# main_board.net
KiCad netlist of a schematic drawn in EAGLE
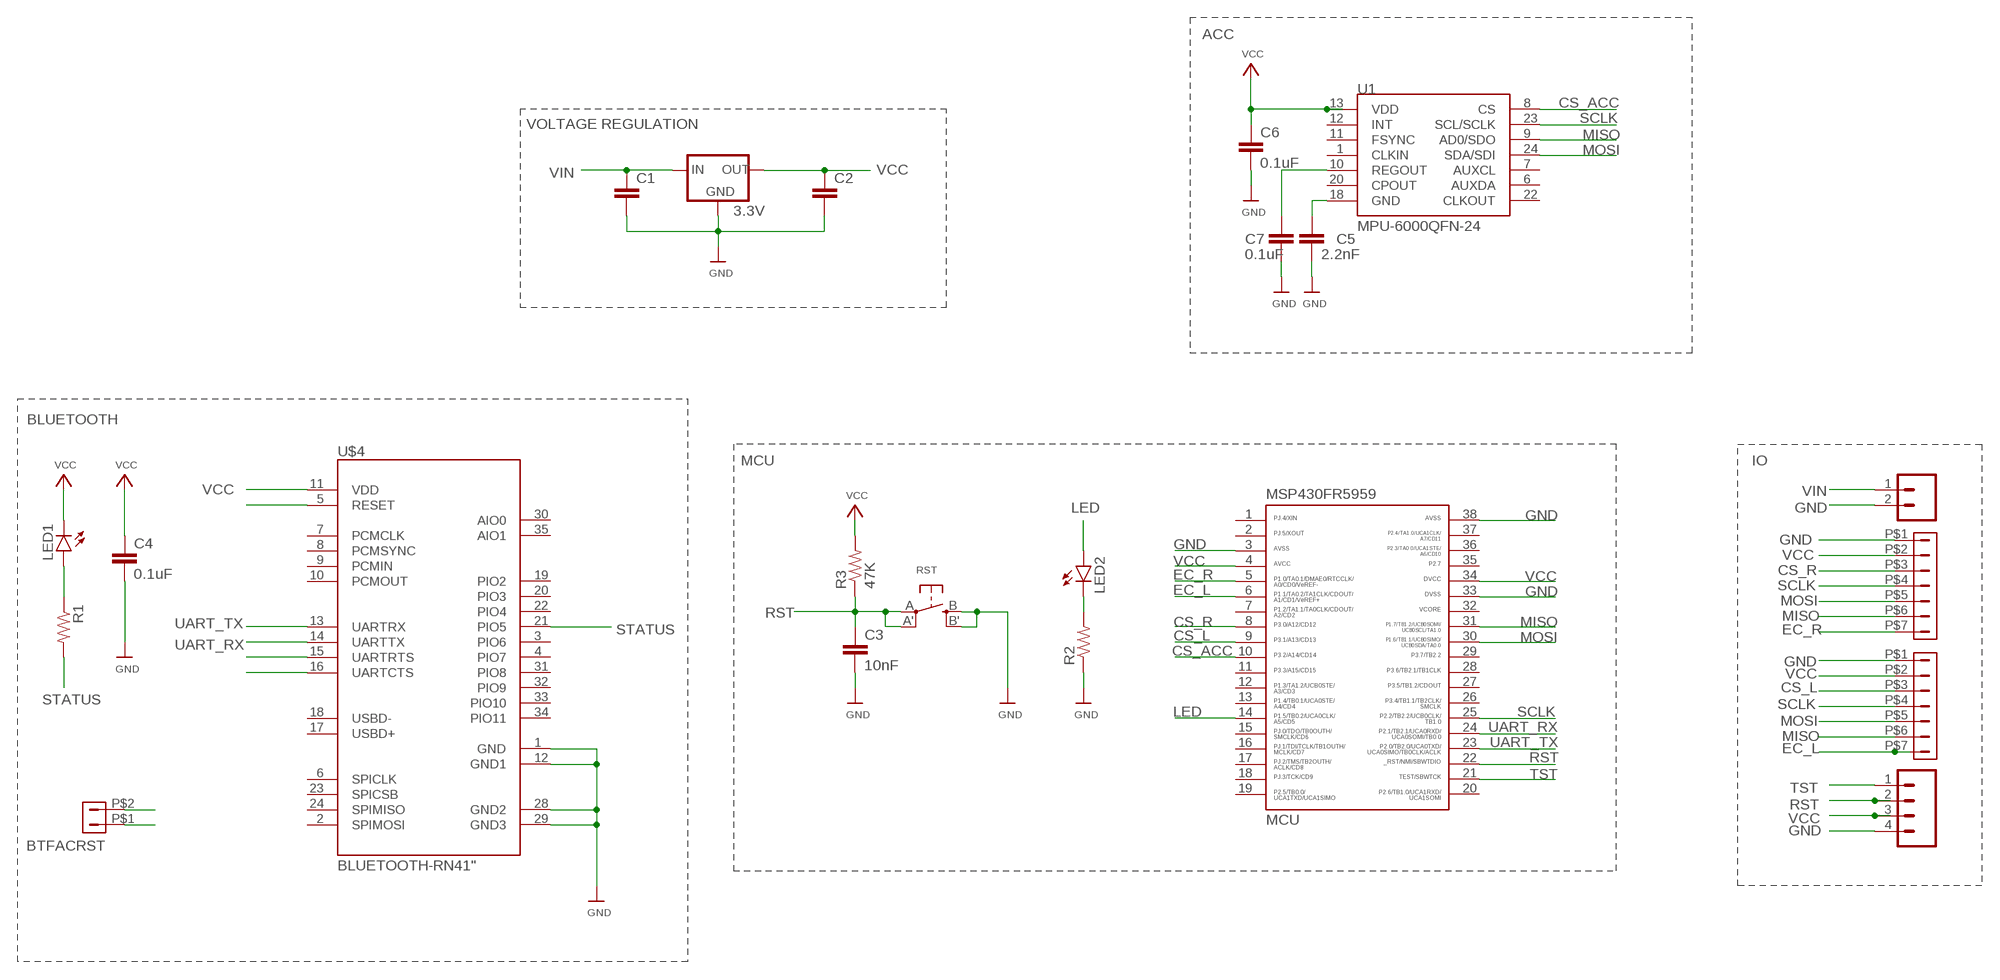
[diagram p0: schematic, sheet 1]

(export (version "E")
  (design (tool "Eeschema 10.0.6"))
  (components
    (comp (ref "3.3V")
      (value "V_REG_78XX")
      (footprint "eagle-import:SOT223")
      (libsource (lib "eagle-import") (part "V_REG_78XX"))
    )
    (comp (ref "5V")
      (value "M02-JST-2-PTH-NO_SILK")
      (footprint "eagle-import:JST-2-PTH-NS")
      (libsource (lib "eagle-import") (part "M02-JST-2-PTH-NO_SILK"))
    )
    (comp (ref "BTFACRST")
      (value "DF13-2P-1.25DSA")
      (footprint "eagle-import:DF13-2P-1.25DSA")
      (libsource (lib "eagle-import") (part "DF13-2P-1.25DSA"))
    )
    (comp (ref "C1")
      (value "CAP0603-CAP")
      (footprint "eagle-import:0603-CAP")
      (libsource (lib "eagle-import") (part "CAP0603-CAP"))
    )
    (comp (ref "C2")
      (value "CAP0603-CAP")
      (footprint "eagle-import:0603-CAP")
      (libsource (lib "eagle-import") (part "CAP0603-CAP"))
    )
    (comp (ref "C3")
      (value "10nF")
      (footprint "eagle-import:0603-CAP")
      (libsource (lib "eagle-import") (part "CAP0603-CAP"))
    )
    (comp (ref "C4")
      (value "0.1uF")
      (footprint "eagle-import:0603-CAP")
      (libsource (lib "eagle-import") (part "CAP0603-CAP"))
    )
    (comp (ref "C5")
      (value "2.2nF")
      (footprint "eagle-import:0402-CAP")
      (libsource (lib "eagle-import") (part "CAP0402-CAP"))
    )
    (comp (ref "C6")
      (value "0.1uF")
      (footprint "eagle-import:0402-CAP")
      (libsource (lib "eagle-import") (part "CAP0402-CAP"))
    )
    (comp (ref "C7")
      (value "0.1uF")
      (footprint "eagle-import:0402-CAP")
      (libsource (lib "eagle-import") (part "CAP0402-CAP"))
    )
    (comp (ref "LED1")
      (value "LED0603")
      (footprint "eagle-import:LED-0603")
      (libsource (lib "eagle-import") (part "LED0603"))
    )
    (comp (ref "LED2")
      (value "LED0603")
      (footprint "eagle-import:LED-0603")
      (libsource (lib "eagle-import") (part "LED0603"))
    )
    (comp (ref "LEFT")
      (value "DF13-7P-1.25DS")
      (footprint "eagle-import:DF13-7P-1.25DS")
      (libsource (lib "eagle-import") (part "DF13-7P-1.25DS"))
    )
    (comp (ref "MCU")
      (value "MSP430FR5959")
      (footprint "eagle-import:TSSOP38_R-PDSO-G38-DA")
      (libsource (lib "eagle-import") (part "MSP430FR5959-38"))
    )
    (comp (ref "PGM")
      (value "M04JST")
      (footprint "eagle-import:1X04-1.5MM_JST")
      (libsource (lib "eagle-import") (part "M04JST"))
    )
    (comp (ref "R1")
      (value "RESISTOR0603-RES")
      (footprint "eagle-import:0603-RES")
      (libsource (lib "eagle-import") (part "RESISTOR0603-RES"))
    )
    (comp (ref "R2")
      (value "RESISTOR0402-RES")
      (footprint "eagle-import:0402-RES")
      (libsource (lib "eagle-import") (part "RESISTOR0402-RES"))
    )
    (comp (ref "R3")
      (value "47K")
      (footprint "eagle-import:0402-RES")
      (libsource (lib "eagle-import") (part "RESISTOR0402-RES"))
    )
    (comp (ref "RIGHT")
      (value "fname")
      (footprint "eagle-import:DF13-7P-1.25DS")
      (libsource (lib "eagle-import") (part "DF13-7P-1.25DS"))
    )
    (comp (ref "RST")
      (value "SWITCH_TACT_SMT")
      (footprint "eagle-import:EVQ-Q2")
      (libsource (lib "eagle-import") (part "SWITCH_TACT_SMT"))
    )
    (comp (ref "U$4")
      (value "BLUETOOTH-RN41\"")
      (footprint "eagle-import:RN41")
      (libsource (lib "eagle-import") (part "BLUETOOTH-RN41{dblquote}"))
    )
    (comp (ref "U1")
      (value "MPU-6000QFN-24")
      (footprint "eagle-import:QFN-24-TESTING")
      (libsource (lib "eagle-import") (part "MPU-6000QFN-24"))
    )
  )
  (nets
    (net (code "1") (name "/BTRST") (class "Default")
      (node (ref "BTFACRST") (pin "P$2") (pinfunction "2_P$2") (pintype "passive"))
      (node (ref "U$4") (pin "5") (pinfunction "RESET_5") (pintype "bidirectional"))
    )
    (net (code "2") (name "/CS_ACC") (class "Default")
      (node (ref "MCU") (pin "10") (pinfunction "10_10") (pintype "bidirectional"))
      (node (ref "U1") (pin "8") (pinfunction "CS_8") (pintype "bidirectional"))
    )
    (net (code "3") (name "/CS_L") (class "Default")
      (node (ref "LEFT") (pin "P$3") (pinfunction "3_P$3") (pintype "passive"))
      (node (ref "MCU") (pin "9") (pinfunction "9_9") (pintype "bidirectional"))
    )
    (net (code "4") (name "/CS_R") (class "Default")
      (node (ref "MCU") (pin "8") (pinfunction "8_8") (pintype "bidirectional"))
      (node (ref "RIGHT") (pin "P$3") (pinfunction "3_P$3") (pintype "passive"))
    )
    (net (code "5") (name "/EC_L") (class "Default")
      (node (ref "LEFT") (pin "P$7") (pinfunction "7_P$7") (pintype "passive"))
      (node (ref "MCU") (pin "6") (pinfunction "6_6") (pintype "bidirectional"))
    )
    (net (code "6") (name "/EC_R") (class "Default")
      (node (ref "MCU") (pin "5") (pinfunction "5_5") (pintype "bidirectional"))
      (node (ref "RIGHT") (pin "P$7") (pinfunction "7_P$7") (pintype "passive"))
    )
    (net (code "7") (name "/LED") (class "Default")
      (node (ref "LED2") (pin "A") (pinfunction "A_A") (pintype "passive"))
      (node (ref "MCU") (pin "14") (pinfunction "14_14") (pintype "bidirectional"))
    )
    (net (code "8") (name "/MISO") (class "Default")
      (node (ref "LEFT") (pin "P$6") (pinfunction "6_P$6") (pintype "passive"))
      (node (ref "MCU") (pin "31") (pinfunction "31_31") (pintype "bidirectional"))
      (node (ref "RIGHT") (pin "P$6") (pinfunction "6_P$6") (pintype "passive"))
      (node (ref "U1") (pin "9") (pinfunction "AD0/SDO_9") (pintype "bidirectional"))
    )
    (net (code "9") (name "/MOSI") (class "Default")
      (node (ref "LEFT") (pin "P$5") (pinfunction "5_P$5") (pintype "passive"))
      (node (ref "MCU") (pin "30") (pinfunction "30_30") (pintype "bidirectional"))
      (node (ref "RIGHT") (pin "P$5") (pinfunction "5_P$5") (pintype "passive"))
      (node (ref "U1") (pin "24") (pinfunction "SDA/SDI_24") (pintype "bidirectional"))
    )
    (net (code "10") (name "/RST") (class "Default")
      (node (ref "C3") (pin "1") (pinfunction "1_1") (pintype "passive"))
      (node (ref "MCU") (pin "22") (pinfunction "22_22") (pintype "bidirectional"))
      (node (ref "PGM") (pin "2") (pinfunction "2_2") (pintype "passive"))
      (node (ref "R3") (pin "1") (pinfunction "1_1") (pintype "passive"))
      (node (ref "RST") (pin "A") (pinfunction "P_A") (pintype "passive"))
      (node (ref "RST") (pin "A'") (pinfunction "P1_A'") (pintype "passive"))
    )
    (net (code "11") (name "/SCLK") (class "Default")
      (node (ref "LEFT") (pin "P$4") (pinfunction "4_P$4") (pintype "passive"))
      (node (ref "MCU") (pin "25") (pinfunction "25_25") (pintype "bidirectional"))
      (node (ref "RIGHT") (pin "P$4") (pinfunction "4_P$4") (pintype "passive"))
      (node (ref "U1") (pin "23") (pinfunction "SCL/SCLK_23") (pintype "bidirectional"))
    )
    (net (code "12") (name "/STATUS") (class "Default")
      (node (ref "R1") (pin "2") (pinfunction "2_2") (pintype "passive"))
      (node (ref "U$4") (pin "21") (pinfunction "PIO5_21") (pintype "bidirectional"))
    )
    (net (code "13") (name "/TST") (class "Default")
      (node (ref "MCU") (pin "21") (pinfunction "21_21") (pintype "bidirectional"))
      (node (ref "PGM") (pin "1") (pinfunction "1_1") (pintype "passive"))
    )
    (net (code "14") (name "/UART_RX") (class "Default")
      (node (ref "MCU") (pin "24") (pinfunction "24_24") (pintype "bidirectional"))
      (node (ref "U$4") (pin "14") (pinfunction "UARTTX_14") (pintype "bidirectional"))
    )
    (net (code "15") (name "/UART_TX") (class "Default")
      (node (ref "MCU") (pin "23") (pinfunction "23_23") (pintype "bidirectional"))
      (node (ref "U$4") (pin "13") (pinfunction "UARTRX_13") (pintype "bidirectional"))
    )
    (net (code "16") (name "/VIN") (class "Default")
      (node (ref "3.3V") (pin "3") (pinfunction "IN_3") (pintype "input"))
      (node (ref "5V") (pin "1") (pinfunction "1_1") (pintype "passive"))
      (node (ref "C1") (pin "1") (pinfunction "1_1") (pintype "passive"))
    )
    (net (code "17") (name "GND") (class "Default")
      (node (ref "3.3V") (pin "2") (pinfunction "GND_2") (pintype "input"))
      (node (ref "3.3V") (pin "4") (pinfunction "GND_4") (pintype "input"))
      (node (ref "5V") (pin "2") (pinfunction "2_2") (pintype "passive"))
      (node (ref "BTFACRST") (pin "P$1") (pinfunction "1_P$1") (pintype "passive"))
      (node (ref "C1") (pin "2") (pinfunction "2_2") (pintype "passive"))
      (node (ref "C2") (pin "2") (pinfunction "2_2") (pintype "passive"))
      (node (ref "C3") (pin "2") (pinfunction "2_2") (pintype "passive"))
      (node (ref "C4") (pin "2") (pinfunction "2_2") (pintype "passive"))
      (node (ref "C5") (pin "2") (pinfunction "2_2") (pintype "passive"))
      (node (ref "C6") (pin "2") (pinfunction "2_2") (pintype "passive"))
      (node (ref "C7") (pin "2") (pinfunction "2_2") (pintype "passive"))
      (node (ref "LEFT") (pin "P$1") (pinfunction "1_P$1") (pintype "passive"))
      (node (ref "MCU") (pin "3") (pinfunction "3_3") (pintype "bidirectional"))
      (node (ref "MCU") (pin "33") (pinfunction "33_33") (pintype "bidirectional"))
      (node (ref "MCU") (pin "38") (pinfunction "38_38") (pintype "bidirectional"))
      (node (ref "PGM") (pin "4") (pinfunction "4_4") (pintype "passive"))
      (node (ref "R2") (pin "1") (pinfunction "1_1") (pintype "passive"))
      (node (ref "RIGHT") (pin "P$1") (pinfunction "1_P$1") (pintype "passive"))
      (node (ref "RST") (pin "B") (pinfunction "S_B") (pintype "passive"))
      (node (ref "RST") (pin "B'") (pinfunction "S1_B'") (pintype "passive"))
      (node (ref "U$4") (pin "1") (pinfunction "GND_1") (pintype "bidirectional"))
      (node (ref "U$4") (pin "12") (pinfunction "GND1_12") (pintype "bidirectional"))
      (node (ref "U$4") (pin "28") (pinfunction "GND2_28") (pintype "bidirectional"))
      (node (ref "U$4") (pin "29") (pinfunction "GND3_29") (pintype "bidirectional"))
    )
    (net (code "18") (name "Net-(LED1-PadA)") (class "Default")
      (node (ref "LED1") (pin "A") (pinfunction "A_A") (pintype "passive"))
      (node (ref "R1") (pin "1") (pinfunction "1_1") (pintype "passive"))
    )
    (net (code "19") (name "Net-(LED2-PadC)") (class "Default")
      (node (ref "LED2") (pin "C") (pinfunction "C_C") (pintype "passive"))
      (node (ref "R2") (pin "2") (pinfunction "2_2") (pintype "passive"))
    )
    (net (code "20") (name "Net-(U1-GND)") (class "Default")
      (node (ref "C5") (pin "1") (pinfunction "1_1") (pintype "passive"))
      (node (ref "U1") (pin "18") (pinfunction "GND_18") (pintype "bidirectional"))
    )
    (net (code "21") (name "Net-(U1-REGOUT)") (class "Default")
      (node (ref "C7") (pin "1") (pinfunction "1_1") (pintype "passive"))
      (node (ref "U1") (pin "10") (pinfunction "REGOUT_10") (pintype "bidirectional"))
    )
    (net (code "22") (name "VCC") (class "Default")
      (node (ref "3.3V") (pin "1") (pinfunction "OUT_1") (pintype "output"))
      (node (ref "C2") (pin "1") (pinfunction "1_1") (pintype "passive"))
      (node (ref "C4") (pin "1") (pinfunction "1_1") (pintype "passive"))
      (node (ref "C6") (pin "1") (pinfunction "1_1") (pintype "passive"))
      (node (ref "LED1") (pin "C") (pinfunction "C_C") (pintype "passive"))
      (node (ref "LEFT") (pin "P$2") (pinfunction "2_P$2") (pintype "passive"))
      (node (ref "MCU") (pin "34") (pinfunction "34_34") (pintype "bidirectional"))
      (node (ref "MCU") (pin "4") (pinfunction "4_4") (pintype "bidirectional"))
      (node (ref "PGM") (pin "3") (pinfunction "3_3") (pintype "passive"))
      (node (ref "R3") (pin "2") (pinfunction "2_2") (pintype "passive"))
      (node (ref "RIGHT") (pin "P$2") (pinfunction "2_P$2") (pintype "passive"))
      (node (ref "U$4") (pin "11") (pinfunction "VDD_11") (pintype "bidirectional"))
      (node (ref "U1") (pin "13") (pinfunction "VDD_13") (pintype "bidirectional"))
    )
    (net (code "23") (name "unconnected-(MCU-Pad1)") (class "Default")
      (node (ref "MCU") (pin "1") (pinfunction "1_1") (pintype "bidirectional"))
    )
    (net (code "24") (name "unconnected-(MCU-Pad2)") (class "Default")
      (node (ref "MCU") (pin "2") (pinfunction "2_2") (pintype "bidirectional"))
    )
    (net (code "25") (name "unconnected-(MCU-Pad7)") (class "Default")
      (node (ref "MCU") (pin "7") (pinfunction "7_7") (pintype "bidirectional"))
    )
    (net (code "26") (name "unconnected-(MCU-Pad11)") (class "Default")
      (node (ref "MCU") (pin "11") (pinfunction "11_11") (pintype "bidirectional"))
    )
    (net (code "27") (name "unconnected-(MCU-Pad12)") (class "Default")
      (node (ref "MCU") (pin "12") (pinfunction "12_12") (pintype "bidirectional"))
    )
    (net (code "28") (name "unconnected-(MCU-Pad13)") (class "Default")
      (node (ref "MCU") (pin "13") (pinfunction "13_13") (pintype "bidirectional"))
    )
    (net (code "29") (name "unconnected-(MCU-Pad15)") (class "Default")
      (node (ref "MCU") (pin "15") (pinfunction "15_15") (pintype "bidirectional"))
    )
    (net (code "30") (name "unconnected-(MCU-Pad16)") (class "Default")
      (node (ref "MCU") (pin "16") (pinfunction "16_16") (pintype "bidirectional"))
    )
    (net (code "31") (name "unconnected-(MCU-Pad17)") (class "Default")
      (node (ref "MCU") (pin "17") (pinfunction "17_17") (pintype "bidirectional"))
    )
    (net (code "32") (name "unconnected-(MCU-Pad18)") (class "Default")
      (node (ref "MCU") (pin "18") (pinfunction "18_18") (pintype "bidirectional"))
    )
    (net (code "33") (name "unconnected-(MCU-Pad19)") (class "Default")
      (node (ref "MCU") (pin "19") (pinfunction "19_19") (pintype "bidirectional"))
    )
    (net (code "34") (name "unconnected-(MCU-Pad20)") (class "Default")
      (node (ref "MCU") (pin "20") (pinfunction "20_20") (pintype "bidirectional"))
    )
    (net (code "35") (name "unconnected-(MCU-Pad26)") (class "Default")
      (node (ref "MCU") (pin "26") (pinfunction "26_26") (pintype "bidirectional"))
    )
    (net (code "36") (name "unconnected-(MCU-Pad27)") (class "Default")
      (node (ref "MCU") (pin "27") (pinfunction "27_27") (pintype "bidirectional"))
    )
    (net (code "37") (name "unconnected-(MCU-Pad28)") (class "Default")
      (node (ref "MCU") (pin "28") (pinfunction "28_28") (pintype "bidirectional"))
    )
    (net (code "38") (name "unconnected-(MCU-Pad29)") (class "Default")
      (node (ref "MCU") (pin "29") (pinfunction "29_29") (pintype "bidirectional"))
    )
    (net (code "39") (name "unconnected-(MCU-Pad32)") (class "Default")
      (node (ref "MCU") (pin "32") (pinfunction "32_32") (pintype "bidirectional"))
    )
    (net (code "40") (name "unconnected-(MCU-Pad35)") (class "Default")
      (node (ref "MCU") (pin "35") (pinfunction "35_35") (pintype "bidirectional"))
    )
    (net (code "41") (name "unconnected-(MCU-Pad36)") (class "Default")
      (node (ref "MCU") (pin "36") (pinfunction "36_36") (pintype "bidirectional"))
    )
    (net (code "42") (name "unconnected-(MCU-Pad37)") (class "Default")
      (node (ref "MCU") (pin "37") (pinfunction "37_37") (pintype "bidirectional"))
    )
    (net (code "43") (name "unconnected-(U$4-AIO0-Pad30)") (class "Default")
      (node (ref "U$4") (pin "30") (pinfunction "AIO0_30") (pintype "bidirectional"))
    )
    (net (code "44") (name "unconnected-(U$4-AIO1-Pad35)") (class "Default")
      (node (ref "U$4") (pin "35") (pinfunction "AIO1_35") (pintype "bidirectional"))
    )
    (net (code "45") (name "unconnected-(U$4-PCMCLK-Pad7)") (class "Default")
      (node (ref "U$4") (pin "7") (pinfunction "PCMCLK_7") (pintype "bidirectional"))
    )
    (net (code "46") (name "unconnected-(U$4-PCMIN-Pad9)") (class "Default")
      (node (ref "U$4") (pin "9") (pinfunction "PCMIN_9") (pintype "bidirectional"))
    )
    (net (code "47") (name "unconnected-(U$4-PCMOUT-Pad10)") (class "Default")
      (node (ref "U$4") (pin "10") (pinfunction "PCMOUT_10") (pintype "bidirectional"))
    )
    (net (code "48") (name "unconnected-(U$4-PCMSYNC-Pad8)") (class "Default")
      (node (ref "U$4") (pin "8") (pinfunction "PCMSYNC_8") (pintype "bidirectional"))
    )
    (net (code "49") (name "unconnected-(U$4-PIO2-Pad19)") (class "Default")
      (node (ref "U$4") (pin "19") (pinfunction "PIO2_19") (pintype "bidirectional"))
    )
    (net (code "50") (name "unconnected-(U$4-PIO3-Pad20)") (class "Default")
      (node (ref "U$4") (pin "20") (pinfunction "PIO3_20") (pintype "bidirectional"))
    )
    (net (code "51") (name "unconnected-(U$4-PIO4-Pad22)") (class "Default")
      (node (ref "U$4") (pin "22") (pinfunction "PIO4_22") (pintype "bidirectional"))
    )
    (net (code "52") (name "unconnected-(U$4-PIO6-Pad3)") (class "Default")
      (node (ref "U$4") (pin "3") (pinfunction "PIO6_3") (pintype "bidirectional"))
    )
    (net (code "53") (name "unconnected-(U$4-PIO7-Pad4)") (class "Default")
      (node (ref "U$4") (pin "4") (pinfunction "PIO7_4") (pintype "bidirectional"))
    )
    (net (code "54") (name "unconnected-(U$4-PIO8-Pad31)") (class "Default")
      (node (ref "U$4") (pin "31") (pinfunction "PIO8_31") (pintype "bidirectional"))
    )
    (net (code "55") (name "unconnected-(U$4-PIO9-Pad32)") (class "Default")
      (node (ref "U$4") (pin "32") (pinfunction "PIO9_32") (pintype "bidirectional"))
    )
    (net (code "56") (name "unconnected-(U$4-PIO10-Pad33)") (class "Default")
      (node (ref "U$4") (pin "33") (pinfunction "PIO10_33") (pintype "bidirectional"))
    )
    (net (code "57") (name "unconnected-(U$4-PIO11-Pad34)") (class "Default")
      (node (ref "U$4") (pin "34") (pinfunction "PIO11_34") (pintype "bidirectional"))
    )
    (net (code "58") (name "unconnected-(U$4-SPICLK-Pad6)") (class "Default")
      (node (ref "U$4") (pin "6") (pinfunction "SPICLK_6") (pintype "bidirectional"))
    )
    (net (code "59") (name "unconnected-(U$4-SPICSB-Pad23)") (class "Default")
      (node (ref "U$4") (pin "23") (pinfunction "SPICSB_23") (pintype "bidirectional"))
    )
    (net (code "60") (name "unconnected-(U$4-SPIMISO-Pad24)") (class "Default")
      (node (ref "U$4") (pin "24") (pinfunction "SPIMISO_24") (pintype "bidirectional"))
    )
    (net (code "61") (name "unconnected-(U$4-SPIMOSI-Pad2)") (class "Default")
      (node (ref "U$4") (pin "2") (pinfunction "SPIMOSI_2") (pintype "bidirectional"))
    )
    (net (code "62") (name "unconnected-(U$4-UARTCTS-Pad16)") (class "Default")
      (node (ref "U$4") (pin "16") (pinfunction "UARTCTS_16") (pintype "bidirectional"))
    )
    (net (code "63") (name "unconnected-(U$4-UARTRTS-Pad15)") (class "Default")
      (node (ref "U$4") (pin "15") (pinfunction "UARTRTS_15") (pintype "bidirectional"))
    )
    (net (code "64") (name "unconnected-(U$4-USBD+-Pad17)") (class "Default")
      (node (ref "U$4") (pin "17") (pinfunction "USBD+_17") (pintype "bidirectional"))
    )
    (net (code "65") (name "unconnected-(U$4-USBD--Pad18)") (class "Default")
      (node (ref "U$4") (pin "18") (pinfunction "USBD-_18") (pintype "bidirectional"))
    )
    (net (code "66") (name "unconnected-(U1-AUXCL-Pad7)") (class "Default")
      (node (ref "U1") (pin "7") (pinfunction "AUXCL_7") (pintype "bidirectional"))
    )
    (net (code "67") (name "unconnected-(U1-AUXDA-Pad6)") (class "Default")
      (node (ref "U1") (pin "6") (pinfunction "AUXDA_6") (pintype "bidirectional"))
    )
    (net (code "68") (name "unconnected-(U1-CLKIN-Pad1)") (class "Default")
      (node (ref "U1") (pin "1") (pinfunction "CLKIN_1") (pintype "bidirectional"))
    )
    (net (code "69") (name "unconnected-(U1-CLKOUT-Pad22)") (class "Default")
      (node (ref "U1") (pin "22") (pinfunction "CLKOUT_22") (pintype "bidirectional"))
    )
    (net (code "70") (name "unconnected-(U1-CPOUT-Pad20)") (class "Default")
      (node (ref "U1") (pin "20") (pinfunction "CPOUT_20") (pintype "bidirectional"))
    )
    (net (code "71") (name "unconnected-(U1-FSYNC-Pad11)") (class "Default")
      (node (ref "U1") (pin "11") (pinfunction "FSYNC_11") (pintype "bidirectional"))
    )
    (net (code "72") (name "unconnected-(U1-INT-Pad12)") (class "Default")
      (node (ref "U1") (pin "12") (pinfunction "INT_12") (pintype "bidirectional"))
    )
  )
)
